# Ethernet.net
KiCad netlist of a schematic drawn in Altium Designer
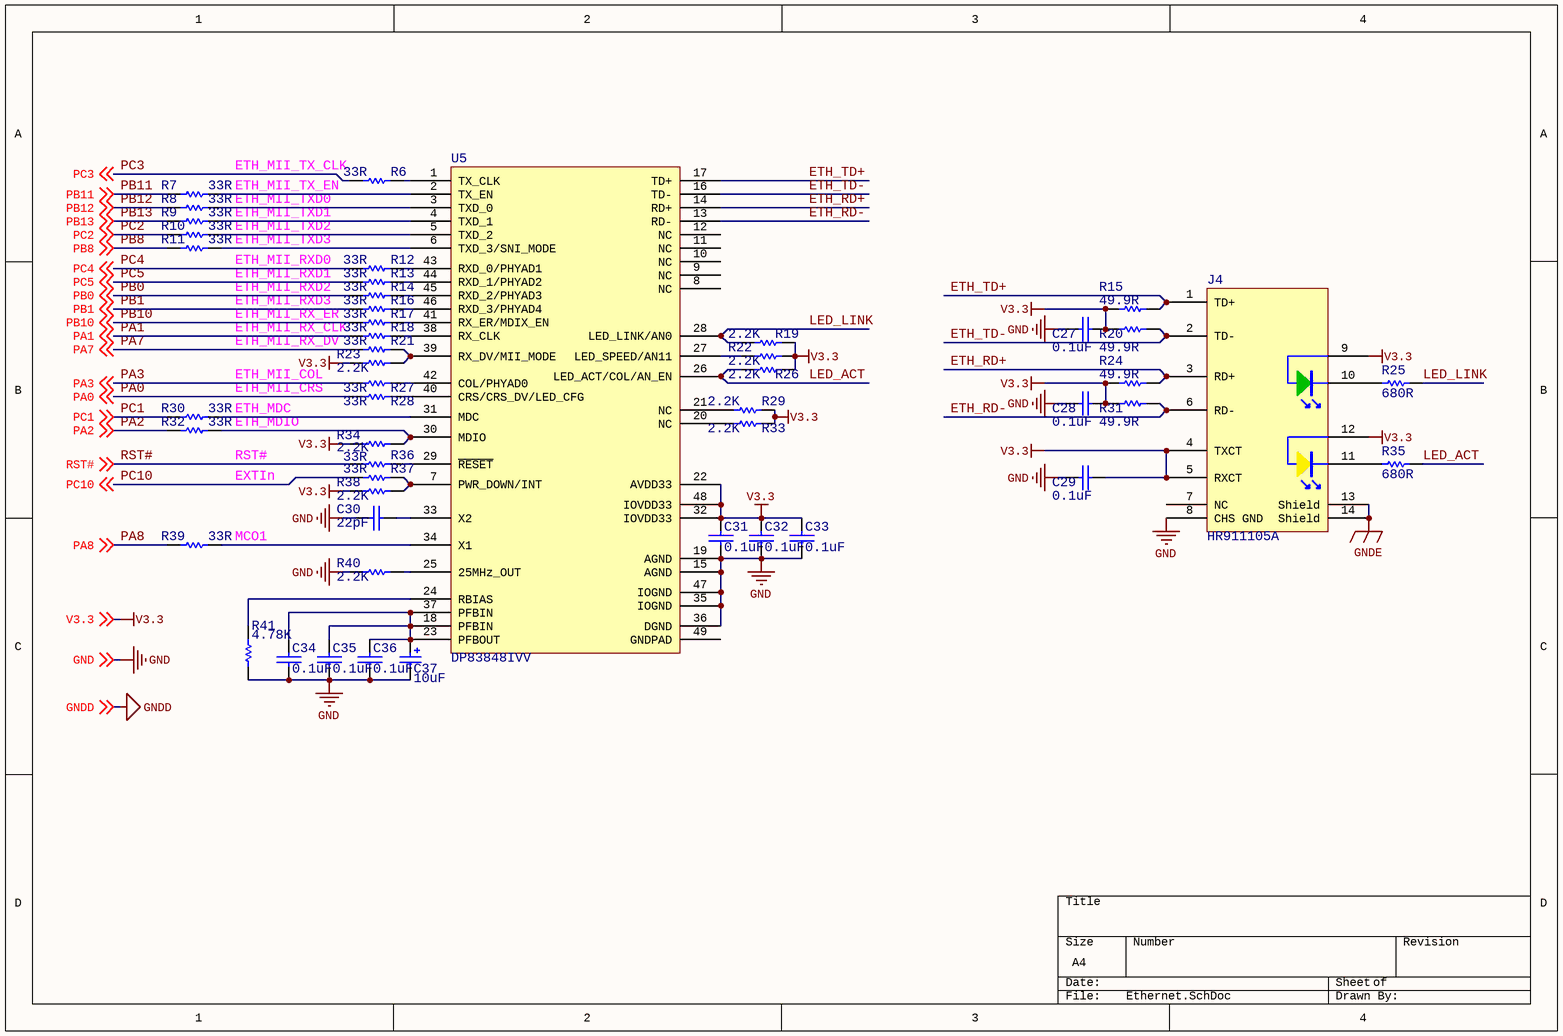
[diagram p0: Ethernet.SchDoc]

(export (version "E")
  (design (tool "Eeschema 10.0.6"))
  (components
    (comp (ref "C27")
      (value "0.1uF")
      (footprint "C1608(0603)")
      (description "Capacitor")
      (libsource (lib "input") (part "CAP"))
    )
    (comp (ref "C28")
      (value "0.1uF")
      (footprint "C1608(0603)")
      (description "Capacitor")
      (libsource (lib "input") (part "CAP"))
    )
    (comp (ref "C29")
      (value "0.1uF")
      (footprint "C1608(0603)")
      (description "Capacitor")
      (libsource (lib "input") (part "CAP"))
    )
    (comp (ref "C30")
      (value "22pF")
      (footprint "C1608(0603)")
      (description "Capacitor")
      (libsource (lib "input") (part "CAP"))
    )
    (comp (ref "C31")
      (value "0.1uF")
      (footprint "C1608(0603)")
      (description "Capacitor")
      (libsource (lib "input") (part "CAP"))
    )
    (comp (ref "C32")
      (value "0.1uF")
      (footprint "C1608(0603)")
      (description "Capacitor")
      (libsource (lib "input") (part "CAP"))
    )
    (comp (ref "C33")
      (value "0.1uF")
      (footprint "C1608(0603)")
      (description "Capacitor")
      (libsource (lib "input") (part "CAP"))
    )
    (comp (ref "C34")
      (value "0.1uF")
      (footprint "C1608(0603)")
      (description "Capacitor")
      (libsource (lib "input") (part "CAP"))
    )
    (comp (ref "C35")
      (value "0.1uF")
      (footprint "C1608(0603)")
      (description "Capacitor")
      (libsource (lib "input") (part "CAP"))
    )
    (comp (ref "C36")
      (value "0.1uF")
      (footprint "C1608(0603)")
      (description "Capacitor")
      (libsource (lib "input") (part "CAP"))
    )
    (comp (ref "C37")
      (value "10uF")
      (footprint "C2012(0805)")
      (description "Polarized Capacitor (Axial)")
      (fields (field (name "PUBLISHER") "Altium Limited"))
      (libsource (lib "Miscellaneous Devices") (part "Cap Pol2"))
    )
    (comp (ref "J4")
      (value "HR911105A")
      (footprint "RJ45-LED")
      (libsource (lib "SL-DPT100") (part "HR911105A"))
    )
    (comp (ref "R6")
      (value "33R")
      (footprint "R1608(0603)")
      (description "Semiconductor Resistor")
      (fields (field (name "PUBLISHER") "Altium Limited"))
      (libsource (lib "Miscellaneous Devices") (part "Res Semi"))
    )
    (comp (ref "R7")
      (value "33R")
      (footprint "R1608(0603)")
      (description "Semiconductor Resistor")
      (fields (field (name "PUBLISHER") "Altium Limited"))
      (libsource (lib "Miscellaneous Devices") (part "Res Semi"))
    )
    (comp (ref "R8")
      (value "33R")
      (footprint "R1608(0603)")
      (description "Semiconductor Resistor")
      (fields (field (name "PUBLISHER") "Altium Limited"))
      (libsource (lib "Miscellaneous Devices") (part "Res Semi"))
    )
    (comp (ref "R9")
      (value "33R")
      (footprint "R1608(0603)")
      (description "Semiconductor Resistor")
      (fields (field (name "PUBLISHER") "Altium Limited"))
      (libsource (lib "Miscellaneous Devices") (part "Res Semi"))
    )
    (comp (ref "R10")
      (value "33R")
      (footprint "R1608(0603)")
      (description "Semiconductor Resistor")
      (fields (field (name "PUBLISHER") "Altium Limited"))
      (libsource (lib "Miscellaneous Devices") (part "Res Semi"))
    )
    (comp (ref "R11")
      (value "33R")
      (footprint "R1608(0603)")
      (description "Semiconductor Resistor")
      (fields (field (name "PUBLISHER") "Altium Limited"))
      (libsource (lib "Miscellaneous Devices") (part "Res Semi"))
    )
    (comp (ref "R12")
      (value "33R")
      (footprint "R1608(0603)")
      (description "Semiconductor Resistor")
      (fields (field (name "PUBLISHER") "Altium Limited"))
      (libsource (lib "Miscellaneous Devices") (part "Res Semi"))
    )
    (comp (ref "R13")
      (value "33R")
      (footprint "R1608(0603)")
      (description "Semiconductor Resistor")
      (fields (field (name "PUBLISHER") "Altium Limited"))
      (libsource (lib "Miscellaneous Devices") (part "Res Semi"))
    )
    (comp (ref "R14")
      (value "33R")
      (footprint "R1608(0603)")
      (description "Semiconductor Resistor")
      (fields (field (name "PUBLISHER") "Altium Limited"))
      (libsource (lib "Miscellaneous Devices") (part "Res Semi"))
    )
    (comp (ref "R15")
      (value "49.9R")
      (footprint "R1608(0603)")
      (description "Semiconductor Resistor")
      (fields (field (name "PUBLISHER") "Altium Limited"))
      (libsource (lib "Miscellaneous Devices") (part "Res Semi"))
    )
    (comp (ref "R16")
      (value "33R")
      (footprint "R1608(0603)")
      (description "Semiconductor Resistor")
      (fields (field (name "PUBLISHER") "Altium Limited"))
      (libsource (lib "Miscellaneous Devices") (part "Res Semi"))
    )
    (comp (ref "R17")
      (value "33R")
      (footprint "R1608(0603)")
      (description "Semiconductor Resistor")
      (fields (field (name "PUBLISHER") "Altium Limited"))
      (libsource (lib "Miscellaneous Devices") (part "Res Semi"))
    )
    (comp (ref "R18")
      (value "33R")
      (footprint "R1608(0603)")
      (description "Semiconductor Resistor")
      (fields (field (name "PUBLISHER") "Altium Limited"))
      (libsource (lib "Miscellaneous Devices") (part "Res Semi"))
    )
    (comp (ref "R19")
      (value "2.2K")
      (footprint "R1608(0603)")
      (description "Semiconductor Resistor")
      (fields (field (name "PUBLISHER") "Altium Limited"))
      (libsource (lib "Miscellaneous Devices") (part "Res Semi"))
    )
    (comp (ref "R20")
      (value "49.9R")
      (footprint "R1608(0603)")
      (description "Semiconductor Resistor")
      (fields (field (name "PUBLISHER") "Altium Limited"))
      (libsource (lib "Miscellaneous Devices") (part "Res Semi"))
    )
    (comp (ref "R21")
      (value "33R")
      (footprint "R1608(0603)")
      (description "Semiconductor Resistor")
      (fields (field (name "PUBLISHER") "Altium Limited"))
      (libsource (lib "Miscellaneous Devices") (part "Res Semi"))
    )
    (comp (ref "R22")
      (value "2.2K")
      (footprint "R1608(0603)")
      (description "Semiconductor Resistor")
      (fields (field (name "PUBLISHER") "Altium Limited"))
      (libsource (lib "Miscellaneous Devices") (part "Res Semi"))
    )
    (comp (ref "R23")
      (value "2.2K")
      (footprint "R1608(0603)")
      (description "Semiconductor Resistor")
      (fields (field (name "PUBLISHER") "Altium Limited"))
      (libsource (lib "Miscellaneous Devices") (part "Res Semi"))
    )
    (comp (ref "R24")
      (value "49.9R")
      (footprint "R1608(0603)")
      (description "Semiconductor Resistor")
      (fields (field (name "PUBLISHER") "Altium Limited"))
      (libsource (lib "Miscellaneous Devices") (part "Res Semi"))
    )
    (comp (ref "R25")
      (value "680R")
      (footprint "R1608(0603)")
      (description "Semiconductor Resistor")
      (fields (field (name "PUBLISHER") "Altium Limited"))
      (libsource (lib "Miscellaneous Devices") (part "Res Semi"))
    )
    (comp (ref "R26")
      (value "2.2K")
      (footprint "R1608(0603)")
      (description "Semiconductor Resistor")
      (fields (field (name "PUBLISHER") "Altium Limited"))
      (libsource (lib "Miscellaneous Devices") (part "Res Semi"))
    )
    (comp (ref "R27")
      (value "33R")
      (footprint "R1608(0603)")
      (description "Semiconductor Resistor")
      (fields (field (name "PUBLISHER") "Altium Limited"))
      (libsource (lib "Miscellaneous Devices") (part "Res Semi"))
    )
    (comp (ref "R28")
      (value "33R")
      (footprint "R1608(0603)")
      (description "Semiconductor Resistor")
      (fields (field (name "PUBLISHER") "Altium Limited"))
      (libsource (lib "Miscellaneous Devices") (part "Res Semi"))
    )
    (comp (ref "R29")
      (value "2.2K")
      (footprint "R1608(0603)")
      (description "Semiconductor Resistor")
      (fields (field (name "PUBLISHER") "Altium Limited"))
      (libsource (lib "Miscellaneous Devices") (part "Res Semi"))
    )
    (comp (ref "R30")
      (value "33R")
      (footprint "R1608(0603)")
      (description "Semiconductor Resistor")
      (fields (field (name "PUBLISHER") "Altium Limited"))
      (libsource (lib "Miscellaneous Devices") (part "Res Semi"))
    )
    (comp (ref "R31")
      (value "49.9R")
      (footprint "R1608(0603)")
      (description "Semiconductor Resistor")
      (fields (field (name "PUBLISHER") "Altium Limited"))
      (libsource (lib "Miscellaneous Devices") (part "Res Semi"))
    )
    (comp (ref "R32")
      (value "33R")
      (footprint "R1608(0603)")
      (description "Semiconductor Resistor")
      (fields (field (name "PUBLISHER") "Altium Limited"))
      (libsource (lib "Miscellaneous Devices") (part "Res Semi"))
    )
    (comp (ref "R33")
      (value "2.2K")
      (footprint "R1608(0603)")
      (description "Semiconductor Resistor")
      (fields (field (name "PUBLISHER") "Altium Limited"))
      (libsource (lib "Miscellaneous Devices") (part "Res Semi"))
    )
    (comp (ref "R34")
      (value "2.2K")
      (footprint "R1608(0603)")
      (description "Semiconductor Resistor")
      (fields (field (name "PUBLISHER") "Altium Limited"))
      (libsource (lib "Miscellaneous Devices") (part "Res Semi"))
    )
    (comp (ref "R35")
      (value "680R")
      (footprint "R1608(0603)")
      (description "Semiconductor Resistor")
      (fields (field (name "PUBLISHER") "Altium Limited"))
      (libsource (lib "Miscellaneous Devices") (part "Res Semi"))
    )
    (comp (ref "R36")
      (value "33R")
      (footprint "R1608(0603)")
      (description "Semiconductor Resistor")
      (fields (field (name "PUBLISHER") "Altium Limited"))
      (libsource (lib "Miscellaneous Devices") (part "Res Semi"))
    )
    (comp (ref "R37")
      (value "33R")
      (footprint "R1608(0603)")
      (description "Semiconductor Resistor")
      (fields (field (name "PUBLISHER") "Altium Limited"))
      (libsource (lib "Miscellaneous Devices") (part "Res Semi"))
    )
    (comp (ref "R38")
      (value "2.2K")
      (footprint "R1608(0603)")
      (description "Semiconductor Resistor")
      (fields (field (name "PUBLISHER") "Altium Limited"))
      (libsource (lib "Miscellaneous Devices") (part "Res Semi"))
    )
    (comp (ref "R39")
      (value "33R")
      (footprint "R1608(0603)")
      (description "Semiconductor Resistor")
      (fields (field (name "PUBLISHER") "Altium Limited"))
      (libsource (lib "Miscellaneous Devices") (part "Res Semi"))
    )
    (comp (ref "R40")
      (value "2.2K")
      (footprint "R1608(0603)")
      (description "Semiconductor Resistor")
      (fields (field (name "PUBLISHER") "Altium Limited"))
      (libsource (lib "Miscellaneous Devices") (part "Res Semi"))
    )
    (comp (ref "R41")
      (value "4.78K")
      (footprint "R1608(0603)")
      (description "Semiconductor Resistor")
      (fields (field (name "PUBLISHER") "Altium Limited"))
      (libsource (lib "Miscellaneous Devices") (part "Res Semi"))
    )
    (comp (ref "U5")
      (value "DP83848IVV")
      (footprint "LQFP48_M")
      (libsource (lib "SL-DPT100") (part "DP83848CVV"))
    )
  )
  (nets
    (net (code "1") (name "/ETH_RD+") (class "Default")
      (node (ref "J4") (pin "3") (pinfunction "RD+_3") (pintype "passive"))
      (node (ref "R24") (pin "1") (pinfunction "1_1") (pintype "passive"))
      (node (ref "U5") (pin "14") (pinfunction "RD+_14") (pintype "passive"))
    )
    (net (code "2") (name "/ETH_RD-") (class "Default")
      (node (ref "J4") (pin "6") (pinfunction "RD-_6") (pintype "passive"))
      (node (ref "R31") (pin "1") (pinfunction "1_1") (pintype "passive"))
      (node (ref "U5") (pin "13") (pinfunction "RD-_13") (pintype "passive"))
    )
    (net (code "3") (name "/ETH_TD+") (class "Default")
      (node (ref "J4") (pin "1") (pinfunction "TD+_1") (pintype "passive"))
      (node (ref "R15") (pin "1") (pinfunction "1_1") (pintype "passive"))
      (node (ref "U5") (pin "17") (pinfunction "TD+_17") (pintype "passive"))
    )
    (net (code "4") (name "/ETH_TD-") (class "Default")
      (node (ref "J4") (pin "2") (pinfunction "TD-_2") (pintype "passive"))
      (node (ref "R20") (pin "1") (pinfunction "1_1") (pintype "passive"))
      (node (ref "U5") (pin "16") (pinfunction "TD-_16") (pintype "passive"))
    )
    (net (code "5") (name "/LED_ACT") (class "Default")
      (node (ref "R26") (pin "2") (pinfunction "2_2") (pintype "passive"))
      (node (ref "R35") (pin "2") (pinfunction "2_2") (pintype "passive"))
      (node (ref "U5") (pin "26") (pinfunction "LED_ACT/COL/AN_EN_26") (pintype "passive"))
    )
    (net (code "6") (name "/LED_LINK") (class "Default")
      (node (ref "R19") (pin "2") (pinfunction "2_2") (pintype "passive"))
      (node (ref "R25") (pin "2") (pinfunction "2_2") (pintype "passive"))
      (node (ref "U5") (pin "28") (pinfunction "LED_LINK/AN0_28") (pintype "passive"))
    )
    (net (code "7") (name "GND") (class "Default")
      (node (ref "C27") (pin "2") (pinfunction "2_2") (pintype "passive"))
      (node (ref "C28") (pin "2") (pinfunction "2_2") (pintype "passive"))
      (node (ref "C29") (pin "2") (pinfunction "2_2") (pintype "passive"))
      (node (ref "C30") (pin "1") (pinfunction "1_1") (pintype "passive"))
      (node (ref "C31") (pin "1") (pinfunction "1_1") (pintype "passive"))
      (node (ref "C32") (pin "1") (pinfunction "1_1") (pintype "passive"))
      (node (ref "C33") (pin "1") (pinfunction "1_1") (pintype "passive"))
      (node (ref "C34") (pin "1") (pinfunction "1_1") (pintype "passive"))
      (node (ref "C35") (pin "1") (pinfunction "1_1") (pintype "passive"))
      (node (ref "C36") (pin "1") (pinfunction "1_1") (pintype "passive"))
      (node (ref "C37") (pin "2") (pinfunction "2_2") (pintype "passive"))
      (node (ref "J4") (pin "8") (pinfunction "CHS_GND_8") (pintype "passive"))
      (node (ref "R40") (pin "2") (pinfunction "2_2") (pintype "passive"))
      (node (ref "R41") (pin "2") (pinfunction "2_2") (pintype "passive"))
      (node (ref "U5") (pin "15") (pinfunction "AGND_15") (pintype "passive"))
      (node (ref "U5") (pin "19") (pinfunction "AGND_19") (pintype "passive"))
      (node (ref "U5") (pin "35") (pinfunction "IOGND_35") (pintype "passive"))
      (node (ref "U5") (pin "36") (pinfunction "DGND_36") (pintype "passive"))
      (node (ref "U5") (pin "47") (pinfunction "IOGND_47") (pintype "passive"))
    )
    (net (code "9") (name "GNDE") (class "Default")
      (node (ref "J4") (pin "13") (pinfunction "Shield_13") (pintype "power_in"))
      (node (ref "J4") (pin "14") (pinfunction "Shield_14") (pintype "power_in"))
    )
    (net (code "10") (name "Net-(J4-Pad10)") (class "Default")
      (node (ref "J4") (pin "10") (pintype "passive"))
      (node (ref "R25") (pin "1") (pinfunction "1_1") (pintype "passive"))
    )
    (net (code "11") (name "Net-(J4-Pad11)") (class "Default")
      (node (ref "J4") (pin "11") (pintype "passive"))
      (node (ref "R35") (pin "1") (pinfunction "1_1") (pintype "passive"))
    )
    (net (code "12") (name "Net-(R29-Pad2)") (class "Default")
      (node (ref "R29") (pin "2") (pinfunction "2_2") (pintype "passive"))
      (node (ref "U5") (pin "21") (pinfunction "NC_21") (pintype "passive"))
    )
    (net (code "13") (name "Net-(R33-Pad2)") (class "Default")
      (node (ref "R33") (pin "2") (pinfunction "2_2") (pintype "passive"))
      (node (ref "U5") (pin "20") (pinfunction "NC_20") (pintype "passive"))
    )
    (net (code "14") (name "Net-(U5-25MHz_OUT)") (class "Default")
      (node (ref "R40") (pin "1") (pinfunction "1_1") (pintype "passive"))
      (node (ref "U5") (pin "25") (pinfunction "25MHz_OUT_25") (pintype "passive"))
    )
    (net (code "15") (name "Net-(U5-COL{slash}PHYAD0)") (class "Default")
      (node (ref "R27") (pin "1") (pinfunction "1_1") (pintype "passive"))
      (node (ref "U5") (pin "42") (pinfunction "COL/PHYAD0_42") (pintype "passive"))
    )
    (net (code "16") (name "Net-(U5-CRS{slash}CRS_DV{slash}LED_CFG)") (class "Default")
      (node (ref "R28") (pin "1") (pinfunction "1_1") (pintype "passive"))
      (node (ref "U5") (pin "40") (pinfunction "CRS/CRS_DV/LED_CFG_40") (pintype "passive"))
    )
    (net (code "17") (name "Net-(U5-LED_SPEED{slash}AN11)") (class "Default")
      (node (ref "R22") (pin "2") (pinfunction "2_2") (pintype "passive"))
      (node (ref "U5") (pin "27") (pinfunction "LED_SPEED/AN11_27") (pintype "passive"))
    )
    (net (code "18") (name "Net-(U5-MDC)") (class "Default")
      (node (ref "R30") (pin "1") (pinfunction "1_1") (pintype "passive"))
      (node (ref "U5") (pin "31") (pinfunction "MDC_31") (pintype "passive"))
    )
    (net (code "19") (name "Net-(U5-MDIO)") (class "Default")
      (node (ref "R32") (pin "1") (pinfunction "1_1") (pintype "passive"))
      (node (ref "R34") (pin "1") (pinfunction "1_1") (pintype "passive"))
      (node (ref "U5") (pin "30") (pinfunction "MDIO_30") (pintype "passive"))
    )
    (net (code "20") (name "Net-(U5-PFBOUT)") (class "Default")
      (node (ref "C34") (pin "2") (pinfunction "2_2") (pintype "passive"))
      (node (ref "C35") (pin "2") (pinfunction "2_2") (pintype "passive"))
      (node (ref "C36") (pin "2") (pinfunction "2_2") (pintype "passive"))
      (node (ref "C37") (pin "1") (pinfunction "1_1") (pintype "passive"))
      (node (ref "U5") (pin "18") (pinfunction "PFBIN_18") (pintype "passive"))
      (node (ref "U5") (pin "23") (pinfunction "PFBOUT_23") (pintype "passive"))
      (node (ref "U5") (pin "37") (pinfunction "PFBIN_37") (pintype "passive"))
    )
    (net (code "21") (name "Net-(U5-PWR_DOWN{slash}INT)") (class "Default")
      (node (ref "R37") (pin "1") (pinfunction "1_1") (pintype "passive"))
      (node (ref "R38") (pin "1") (pinfunction "1_1") (pintype "passive"))
      (node (ref "U5") (pin "7") (pinfunction "PWR_DOWN/INT_7") (pintype "passive"))
    )
    (net (code "22") (name "Net-(U5-RBIAS)") (class "Default")
      (node (ref "R41") (pin "1") (pinfunction "1_1") (pintype "passive"))
      (node (ref "U5") (pin "24") (pinfunction "RBIAS_24") (pintype "passive"))
    )
    (net (code "23") (name "Net-(U5-RXD_0{slash}PHYAD1)") (class "Default")
      (node (ref "R12") (pin "1") (pinfunction "1_1") (pintype "passive"))
      (node (ref "U5") (pin "43") (pinfunction "RXD_0/PHYAD1_43") (pintype "passive"))
    )
    (net (code "24") (name "Net-(U5-RXD_1{slash}PHYAD2)") (class "Default")
      (node (ref "R13") (pin "1") (pinfunction "1_1") (pintype "passive"))
      (node (ref "U5") (pin "44") (pinfunction "RXD_1/PHYAD2_44") (pintype "passive"))
    )
    (net (code "25") (name "Net-(U5-RXD_2{slash}PHYAD3)") (class "Default")
      (node (ref "R14") (pin "1") (pinfunction "1_1") (pintype "passive"))
      (node (ref "U5") (pin "45") (pinfunction "RXD_2/PHYAD3_45") (pintype "passive"))
    )
    (net (code "26") (name "Net-(U5-RXD_3{slash}PHYAD4)") (class "Default")
      (node (ref "R16") (pin "1") (pinfunction "1_1") (pintype "passive"))
      (node (ref "U5") (pin "46") (pinfunction "RXD_3/PHYAD4_46") (pintype "passive"))
    )
    (net (code "27") (name "Net-(U5-RX_CLK)") (class "Default")
      (node (ref "R18") (pin "1") (pinfunction "1_1") (pintype "passive"))
      (node (ref "U5") (pin "38") (pinfunction "RX_CLK_38") (pintype "passive"))
    )
    (net (code "28") (name "Net-(U5-RX_DV{slash}MII_MODE)") (class "Default")
      (node (ref "R21") (pin "1") (pinfunction "1_1") (pintype "passive"))
      (node (ref "R23") (pin "1") (pinfunction "1_1") (pintype "passive"))
      (node (ref "U5") (pin "39") (pinfunction "RX_DV/MII_MODE_39") (pintype "passive"))
    )
    (net (code "29") (name "Net-(U5-RX_ER{slash}MDIX_EN)") (class "Default")
      (node (ref "R17") (pin "1") (pinfunction "1_1") (pintype "passive"))
      (node (ref "U5") (pin "41") (pinfunction "RX_ER/MDIX_EN_41") (pintype "passive"))
    )
    (net (code "30") (name "Net-(U5-TXD_0)") (class "Default")
      (node (ref "R8") (pin "1") (pinfunction "1_1") (pintype "passive"))
      (node (ref "U5") (pin "3") (pinfunction "TXD_0_3") (pintype "passive"))
    )
    (net (code "31") (name "Net-(U5-TXD_1)") (class "Default")
      (node (ref "R9") (pin "1") (pinfunction "1_1") (pintype "passive"))
      (node (ref "U5") (pin "4") (pinfunction "TXD_1_4") (pintype "passive"))
    )
    (net (code "32") (name "Net-(U5-TXD_2)") (class "Default")
      (node (ref "R10") (pin "1") (pinfunction "1_1") (pintype "passive"))
      (node (ref "U5") (pin "5") (pinfunction "TXD_2_5") (pintype "passive"))
    )
    (net (code "33") (name "Net-(U5-TXD_3{slash}SNI_MODE)") (class "Default")
      (node (ref "R11") (pin "1") (pinfunction "1_1") (pintype "passive"))
      (node (ref "U5") (pin "6") (pinfunction "TXD_3/SNI_MODE_6") (pintype "passive"))
    )
    (net (code "34") (name "Net-(U5-TX_CLK)") (class "Default")
      (node (ref "R6") (pin "1") (pinfunction "1_1") (pintype "passive"))
      (node (ref "U5") (pin "1") (pinfunction "TX_CLK_1") (pintype "passive"))
    )
    (net (code "35") (name "Net-(U5-TX_EN)") (class "Default")
      (node (ref "R7") (pin "1") (pinfunction "1_1") (pintype "passive"))
      (node (ref "U5") (pin "2") (pinfunction "TX_EN_2") (pintype "passive"))
    )
    (net (code "36") (name "Net-(U5-X1)") (class "Default")
      (node (ref "R39") (pin "1") (pinfunction "1_1") (pintype "passive"))
      (node (ref "U5") (pin "34") (pinfunction "X1_34") (pintype "passive"))
    )
    (net (code "37") (name "Net-(U5-X2)") (class "Default")
      (node (ref "C30") (pin "2") (pinfunction "2_2") (pintype "passive"))
      (node (ref "U5") (pin "33") (pinfunction "X2_33") (pintype "passive"))
    )
    (net (code "38") (name "Net-(U5-~{RESET})") (class "Default")
      (node (ref "R36") (pin "1") (pinfunction "1_1") (pintype "passive"))
      (node (ref "U5") (pin "29") (pinfunction "~{RESET}_29") (pintype "passive"))
    )
    (net (code "39") (name "PA0") (class "Default")
      (node (ref "R28") (pin "2") (pinfunction "2_2") (pintype "passive"))
    )
    (net (code "40") (name "PA1") (class "Default")
      (node (ref "R18") (pin "2") (pinfunction "2_2") (pintype "passive"))
    )
    (net (code "41") (name "PA2") (class "Default")
      (node (ref "R32") (pin "2") (pinfunction "2_2") (pintype "passive"))
    )
    (net (code "42") (name "PA3") (class "Default")
      (node (ref "R27") (pin "2") (pinfunction "2_2") (pintype "passive"))
    )
    (net (code "43") (name "PA7") (class "Default")
      (node (ref "R21") (pin "2") (pinfunction "2_2") (pintype "passive"))
    )
    (net (code "44") (name "PA8") (class "Default")
      (node (ref "R39") (pin "2") (pinfunction "2_2") (pintype "passive"))
    )
    (net (code "45") (name "PB0") (class "Default")
      (node (ref "R14") (pin "2") (pinfunction "2_2") (pintype "passive"))
    )
    (net (code "46") (name "PB1") (class "Default")
      (node (ref "R16") (pin "2") (pinfunction "2_2") (pintype "passive"))
    )
    (net (code "47") (name "PB8") (class "Default")
      (node (ref "R11") (pin "2") (pinfunction "2_2") (pintype "passive"))
    )
    (net (code "48") (name "PB10") (class "Default")
      (node (ref "R17") (pin "2") (pinfunction "2_2") (pintype "passive"))
    )
    (net (code "49") (name "PB11") (class "Default")
      (node (ref "R7") (pin "2") (pinfunction "2_2") (pintype "passive"))
    )
    (net (code "50") (name "PB12") (class "Default")
      (node (ref "R8") (pin "2") (pinfunction "2_2") (pintype "passive"))
    )
    (net (code "51") (name "PB13") (class "Default")
      (node (ref "R9") (pin "2") (pinfunction "2_2") (pintype "passive"))
    )
    (net (code "52") (name "PC1") (class "Default")
      (node (ref "R30") (pin "2") (pinfunction "2_2") (pintype "passive"))
    )
    (net (code "53") (name "PC2") (class "Default")
      (node (ref "R10") (pin "2") (pinfunction "2_2") (pintype "passive"))
    )
    (net (code "54") (name "PC3") (class "Default")
      (node (ref "R6") (pin "2") (pinfunction "2_2") (pintype "passive"))
    )
    (net (code "55") (name "PC4") (class "Default")
      (node (ref "R12") (pin "2") (pinfunction "2_2") (pintype "passive"))
    )
    (net (code "56") (name "PC5") (class "Default")
      (node (ref "R13") (pin "2") (pinfunction "2_2") (pintype "passive"))
    )
    (net (code "57") (name "PC10") (class "Default")
      (node (ref "R37") (pin "2") (pinfunction "2_2") (pintype "passive"))
    )
    (net (code "58") (name "RST#") (class "Default")
      (node (ref "R36") (pin "2") (pinfunction "2_2") (pintype "passive"))
    )
    (net (code "59") (name "V3.3") (class "Default")
      (node (ref "C27") (pin "1") (pinfunction "1_1") (pintype "passive"))
      (node (ref "C28") (pin "1") (pinfunction "1_1") (pintype "passive"))
      (node (ref "C29") (pin "1") (pinfunction "1_1") (pintype "passive"))
      (node (ref "C31") (pin "2") (pinfunction "2_2") (pintype "passive"))
      (node (ref "C32") (pin "2") (pinfunction "2_2") (pintype "passive"))
      (node (ref "C33") (pin "2") (pinfunction "2_2") (pintype "passive"))
      (node (ref "J4") (pin "12") (pintype "passive"))
      (node (ref "J4") (pin "4") (pinfunction "TXCT_4") (pintype "passive"))
      (node (ref "J4") (pin "5") (pinfunction "RXCT_5") (pintype "passive"))
      (node (ref "J4") (pin "9") (pintype "passive"))
      (node (ref "R15") (pin "2") (pinfunction "2_2") (pintype "passive"))
      (node (ref "R19") (pin "1") (pinfunction "1_1") (pintype "passive"))
      (node (ref "R20") (pin "2") (pinfunction "2_2") (pintype "passive"))
      (node (ref "R22") (pin "1") (pinfunction "1_1") (pintype "passive"))
      (node (ref "R23") (pin "2") (pinfunction "2_2") (pintype "passive"))
      (node (ref "R24") (pin "2") (pinfunction "2_2") (pintype "passive"))
      (node (ref "R26") (pin "1") (pinfunction "1_1") (pintype "passive"))
      (node (ref "R29") (pin "1") (pinfunction "1_1") (pintype "passive"))
      (node (ref "R31") (pin "2") (pinfunction "2_2") (pintype "passive"))
      (node (ref "R33") (pin "1") (pinfunction "1_1") (pintype "passive"))
      (node (ref "R34") (pin "2") (pinfunction "2_2") (pintype "passive"))
      (node (ref "R38") (pin "2") (pinfunction "2_2") (pintype "passive"))
      (node (ref "U5") (pin "22") (pinfunction "AVDD33_22") (pintype "passive"))
      (node (ref "U5") (pin "32") (pinfunction "IOVDD33_32") (pintype "passive"))
      (node (ref "U5") (pin "48") (pinfunction "IOVDD33_48") (pintype "passive"))
    )
    (net (code "60") (name "unconnected-(J4-NC-Pad7)") (class "Default")
      (node (ref "J4") (pin "7") (pinfunction "NC_7") (pintype "passive"))
    )
    (net (code "61") (name "unconnected-(U5-GNDPAD-Pad49)") (class "Default")
      (node (ref "U5") (pin "49") (pinfunction "GNDPAD_49") (pintype "power_in"))
    )
    (net (code "62") (name "unconnected-(U5-NC-Pad8)") (class "Default")
      (node (ref "U5") (pin "8") (pinfunction "NC_8") (pintype "passive"))
    )
    (net (code "63") (name "unconnected-(U5-NC-Pad9)") (class "Default")
      (node (ref "U5") (pin "9") (pinfunction "NC_9") (pintype "passive"))
    )
    (net (code "64") (name "unconnected-(U5-NC-Pad10)") (class "Default")
      (node (ref "U5") (pin "10") (pinfunction "NC_10") (pintype "passive"))
    )
    (net (code "65") (name "unconnected-(U5-NC-Pad11)") (class "Default")
      (node (ref "U5") (pin "11") (pinfunction "NC_11") (pintype "passive"))
    )
    (net (code "66") (name "unconnected-(U5-NC-Pad12)") (class "Default")
      (node (ref "U5") (pin "12") (pinfunction "NC_12") (pintype "passive"))
    )
  )
)
